# ArtixTranscievers.net
KiCad netlist of a schematic drawn in Altium Designer
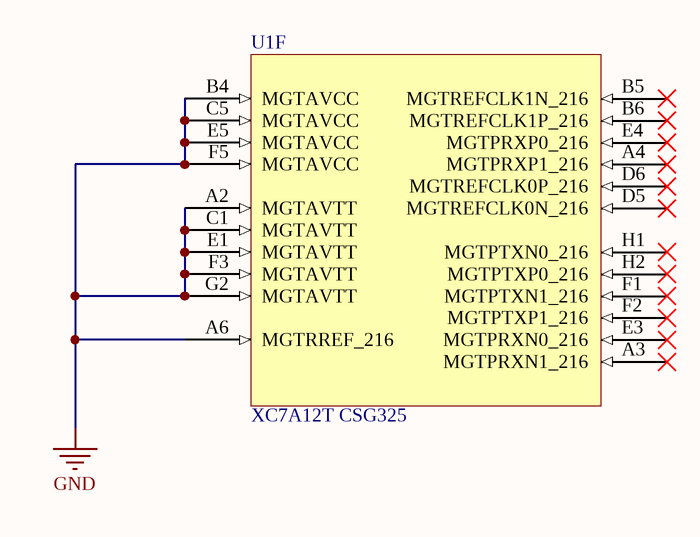
[diagram p0: ArtixTranscievers.SchDoc]

(export (version "E")
  (design (tool "Eeschema 10.0.6"))
  (components
    (comp (ref "U1")
      (value "XC7A12T CSG325")
      (footprint "BGA324C80P18X18_1500X1500X150")
      (libsource (lib "XC7A12T_1CPG238I") (part "XC7A12T_1CSG325I"))
    )
  )
  (nets
    (net (code "1") (name "GND") (class "Default")
      (node (ref "U1") (pin "A2") (pinfunction "MGTAVTT_A2") (pintype "input"))
      (node (ref "U1") (pin "A6") (pinfunction "MGTRREF_216_A6") (pintype "input"))
      (node (ref "U1") (pin "B4") (pinfunction "MGTAVCC_B4") (pintype "input"))
      (node (ref "U1") (pin "C1") (pinfunction "MGTAVTT_C1") (pintype "input"))
      (node (ref "U1") (pin "C5") (pinfunction "MGTAVCC_C5") (pintype "input"))
      (node (ref "U1") (pin "E1") (pinfunction "MGTAVTT_E1") (pintype "input"))
      (node (ref "U1") (pin "E5") (pinfunction "MGTAVCC_E5") (pintype "input"))
      (node (ref "U1") (pin "F3") (pinfunction "MGTAVTT_F3") (pintype "input"))
      (node (ref "U1") (pin "F5") (pinfunction "MGTAVCC_F5") (pintype "input"))
      (node (ref "U1") (pin "G2") (pinfunction "MGTAVTT_G2") (pintype "input"))
    )
    (net (code "2") (name "unconnected-(U1F-MGTPRXN0_216-PadE3)") (class "Default")
      (node (ref "U1") (pin "E3") (pinfunction "MGTPRXN0_216_E3") (pintype "input+no_connect"))
    )
    (net (code "3") (name "unconnected-(U1F-MGTPRXN1_216-PadA3)") (class "Default")
      (node (ref "U1") (pin "A3") (pinfunction "MGTPRXN1_216_A3") (pintype "input+no_connect"))
    )
    (net (code "4") (name "unconnected-(U1F-MGTPRXP0_216-PadE4)") (class "Default")
      (node (ref "U1") (pin "E4") (pinfunction "MGTPRXP0_216_E4") (pintype "input+no_connect"))
    )
    (net (code "5") (name "unconnected-(U1F-MGTPRXP1_216-PadA4)") (class "Default")
      (node (ref "U1") (pin "A4") (pinfunction "MGTPRXP1_216_A4") (pintype "input+no_connect"))
    )
    (net (code "6") (name "unconnected-(U1F-MGTPTXN0_216-PadH1)") (class "Default")
      (node (ref "U1") (pin "H1") (pinfunction "MGTPTXN0_216_H1") (pintype "input+no_connect"))
    )
    (net (code "7") (name "unconnected-(U1F-MGTPTXN1_216-PadF1)") (class "Default")
      (node (ref "U1") (pin "F1") (pinfunction "MGTPTXN1_216_F1") (pintype "input+no_connect"))
    )
    (net (code "8") (name "unconnected-(U1F-MGTPTXP0_216-PadH2)") (class "Default")
      (node (ref "U1") (pin "H2") (pinfunction "MGTPTXP0_216_H2") (pintype "input+no_connect"))
    )
    (net (code "9") (name "unconnected-(U1F-MGTPTXP1_216-PadF2)") (class "Default")
      (node (ref "U1") (pin "F2") (pinfunction "MGTPTXP1_216_F2") (pintype "input+no_connect"))
    )
    (net (code "10") (name "unconnected-(U1F-MGTREFCLK0N_216-PadD5)") (class "Default")
      (node (ref "U1") (pin "D5") (pinfunction "MGTREFCLK0N_216_D5") (pintype "input+no_connect"))
    )
    (net (code "11") (name "unconnected-(U1F-MGTREFCLK0P_216-PadD6)") (class "Default")
      (node (ref "U1") (pin "D6") (pinfunction "MGTREFCLK0P_216_D6") (pintype "input+no_connect"))
    )
    (net (code "12") (name "unconnected-(U1F-MGTREFCLK1N_216-PadB5)") (class "Default")
      (node (ref "U1") (pin "B5") (pinfunction "MGTREFCLK1N_216_B5") (pintype "input+no_connect"))
    )
    (net (code "13") (name "unconnected-(U1F-MGTREFCLK1P_216-PadB6)") (class "Default")
      (node (ref "U1") (pin "B6") (pinfunction "MGTREFCLK1P_216_B6") (pintype "input+no_connect"))
    )
  )
)
